# Mixer_to_Low_Pass_Filter.net
KiCad netlist of a schematic drawn in Altium Designer
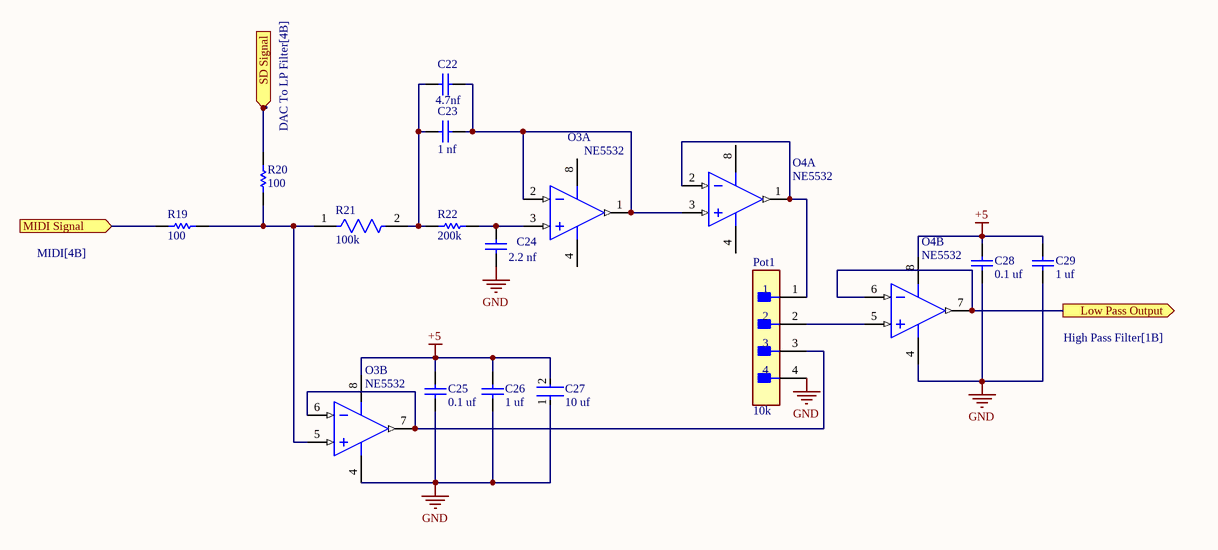
[diagram p0: Mixer to Low Pass Filter.SchDoc]

(export (version "E")
  (design (tool "Eeschema 10.0.6"))
  (components
    (comp (ref "C22")
      (value "4.7nf")
      (footprint "AVX-SA115C104KAR")
      (fields (field (name "TOLERANCE") "±10%") (field (name "MANUFACTURER") "AVX"))
      (libsource (lib "Altium Content Vault") (part "CAP-NP-2"))
    )
    (comp (ref "C23")
      (value "1 nf")
      (footprint "AVX-SA115C104KAR")
      (fields (field (name "TOLERANCE") "±10%") (field (name "MANUFACTURER") "AVX"))
      (libsource (lib "Altium Content Vault") (part "CAP-NP-2"))
    )
    (comp (ref "C24")
      (value "2.2 nf")
      (footprint "AVX-SA115C104KAR")
      (fields (field (name "TOLERANCE") "±10%") (field (name "MANUFACTURER") "AVX"))
      (libsource (lib "Altium Content Vault") (part "CAP-NP-2"))
    )
    (comp (ref "C25")
      (value "0.1 uf")
      (footprint "CAPC2013X135X45ML10T25")
      (description "Chip Capacitor, 0.1 uF, +/- 10%, 50 V, -55 to 125 degC, 0805 (2012 Metric), RoHS, Tape and Reel")
      (fields (field (name "VOLTAGE") "50V") (field (name "TOLERANCE") "10%"))
      (libsource (lib "Altium Content Vault") (part "CAP-NP-2"))
    )
    (comp (ref "C26")
      (value "1 uf")
      (footprint "CAPC2013X145X50LL20T25")
      (fields (field (name "MANUFACTURER") "Kemet") (field (name "PART NUMBER") "C0805C105K4PACTU"))
      (libsource (lib "Altium Content Vault") (part "CAP"))
    )
    (comp (ref "C27")
      (value "10 uf")
      (footprint "FP-C0805C-DG-MFG")
      (description "CAP CER 10UF 10V X5R 0805")
      (fields (field (name "TOLERANCE") "10%") (field (name "MANUFACTURER PART NUMBER") "C0805C106K8PACTU"))
      (libsource (lib "Altium Content Vault") (part "11868f565c42a9108669ba33697ecf6"))
    )
    (comp (ref "C28")
      (value "0.1 uf")
      (footprint "CAPC2013X135X45ML10T25")
      (description "Chip Capacitor, 0.1 uF, +/- 10%, 50 V, -55 to 125 degC, 0805 (2012 Metric), RoHS, Tape and Reel")
      (fields (field (name "VOLTAGE") "50V") (field (name "TOLERANCE") "10%"))
      (libsource (lib "Altium Content Vault") (part "CAP-NP-2"))
    )
    (comp (ref "C29")
      (value "1 uf")
      (footprint "CAPC2013X145X50LL20T25")
      (fields (field (name "MANUFACTURER") "Kemet") (field (name "PART NUMBER") "C0805C105K4PACTU"))
      (libsource (lib "Altium Content Vault") (part "CAP"))
    )
    (comp (ref "O3")
      (value "NE5532")
      (footprint "ONSC-SOIC-8-751-07_V")
      (fields (field (name "MANUFACTURER") "On Semiconductor") (field (name "PARTNUMBER") "NE5532AD8R2G"))
      (libsource (lib "Altium Content Vault") (part "ONSC-NE5532-SOIC-8-751-07"))
    )
    (comp (ref "O4")
      (value "NE5532")
      (footprint "ONSC-SOIC-8-751-07_V")
      (fields (field (name "MANUFACTURER") "On Semiconductor") (field (name "PARTNUMBER") "NE5532AD8R2G"))
      (libsource (lib "Altium Content Vault") (part "ONSC-NE5532-SOIC-8-751-07"))
    )
    (comp (ref "Pot1")
      (value "10k")
      (footprint "FP-B4B-XH-A_LF_SN-MFG")
      (description "CONN HEADER VERT 4POS 2.5MM")
      (libsource (lib "Altium Content Vault") (part "299a8cea1bdcbc3624fe62c390fa72c"))
    )
    (comp (ref "R19")
      (value "100")
      (footprint "RESC2013X60X40ML20T25")
      (fields (field (name "MANUFACTURER") "Panasonic") (field (name "PART NUMBER") "ERA6AEB101V"))
      (libsource (lib "Altium Content Vault") (part "RES"))
    )
    (comp (ref "R20")
      (value "100")
      (footprint "RESC2013X60X40ML20T25")
      (fields (field (name "MANUFACTURER") "Panasonic") (field (name "PART NUMBER") "ERA6AEB101V"))
      (libsource (lib "Altium Content Vault") (part "RES"))
    )
    (comp (ref "R21")
      (value "100k")
      (footprint "FP-RC0805-0_6-IPC_C")
      (description "RES 100K OHM 1% 1/8W 0805")
      (fields (field (name "TOLERANCE") "1%"))
      (libsource (lib "Altium Content Vault") (part "1029c3af85768c4190bb7ad29bc67b5"))
    )
    (comp (ref "R22")
      (value "200k")
      (footprint "RESC2013X60X40LL20T25")
      (fields (field (name "PART NUMBER") "ERA6AEB204V") (field (name "MANUFACTURER") "Panasonic"))
      (libsource (lib "Altium Content Vault") (part "RES"))
    )
  )
  (nets
    (net (code "1") (name "+5") (class "Default")
      (node (ref "C25") (pin "1") (pinfunction "1_1") (pintype "passive"))
      (node (ref "C26") (pin "1") (pinfunction "1_1") (pintype "passive"))
      (node (ref "C27") (pin "2") (pinfunction "2_2") (pintype "passive"))
      (node (ref "C28") (pin "1") (pinfunction "1_1") (pintype "passive"))
      (node (ref "C29") (pin "1") (pinfunction "1_1") (pintype "passive"))
      (node (ref "O3") (pin "8") (pinfunction "V+_8") (pintype "power_in"))
      (node (ref "O4") (pin "8") (pinfunction "V+_8") (pintype "power_in"))
    )
    (net (code "2") (name "/Low Pass Output") (class "Default")
      (node (ref "O4") (pin "6") (pinfunction "INB-_6") (pintype "input"))
      (node (ref "O4") (pin "7") (pinfunction "OUTB_7") (pintype "output"))
    )
    (net (code "3") (name "/MIDI Signal") (class "Default")
      (node (ref "R19") (pin "1") (pinfunction "1_1") (pintype "passive"))
    )
    (net (code "4") (name "/SD Signal") (class "Default")
      (node (ref "R20") (pin "1") (pinfunction "1_1") (pintype "passive"))
    )
    (net (code "5") (name "GND") (class "Default")
      (node (ref "C24") (pin "1") (pinfunction "1_1") (pintype "passive"))
      (node (ref "C25") (pin "2") (pinfunction "2_2") (pintype "passive"))
      (node (ref "C26") (pin "2") (pinfunction "2_2") (pintype "passive"))
      (node (ref "C27") (pin "1") (pinfunction "1_1") (pintype "passive"))
      (node (ref "C28") (pin "2") (pinfunction "2_2") (pintype "passive"))
      (node (ref "C29") (pin "2") (pinfunction "2_2") (pintype "passive"))
      (node (ref "O3") (pin "4") (pinfunction "V-_4") (pintype "power_in"))
      (node (ref "O4") (pin "4") (pinfunction "V-_4") (pintype "power_in"))
      (node (ref "Pot1") (pin "4") (pinfunction "4_4") (pintype "passive"))
    )
    (net (code "6") (name "Net-(C22-Pad1)") (class "Default")
      (node (ref "C22") (pin "1") (pinfunction "1_1") (pintype "passive"))
      (node (ref "C23") (pin "1") (pinfunction "1_1") (pintype "passive"))
      (node (ref "R21") (pin "2") (pinfunction "2_2") (pintype "passive"))
      (node (ref "R22") (pin "1") (pinfunction "1_1") (pintype "passive"))
    )
    (net (code "7") (name "Net-(O3A-INA+)") (class "Default")
      (node (ref "C24") (pin "2") (pinfunction "2_2") (pintype "passive"))
      (node (ref "O3") (pin "3") (pinfunction "INA+_3") (pintype "input"))
      (node (ref "R22") (pin "2") (pinfunction "2_2") (pintype "passive"))
    )
    (net (code "8") (name "Net-(O3A-INA-)") (class "Default")
      (node (ref "C22") (pin "2") (pinfunction "2_2") (pintype "passive"))
      (node (ref "C23") (pin "2") (pinfunction "2_2") (pintype "passive"))
      (node (ref "O3") (pin "1") (pinfunction "OUTA_1") (pintype "output"))
      (node (ref "O3") (pin "2") (pinfunction "INA-_2") (pintype "input"))
      (node (ref "O4") (pin "3") (pinfunction "INA+_3") (pintype "input"))
    )
    (net (code "9") (name "Net-(O3B-INB+)") (class "Default")
      (node (ref "O3") (pin "5") (pinfunction "INB+_5") (pintype "input"))
      (node (ref "R19") (pin "2") (pinfunction "2_2") (pintype "passive"))
      (node (ref "R20") (pin "2") (pinfunction "2_2") (pintype "passive"))
      (node (ref "R21") (pin "1") (pinfunction "1_1") (pintype "passive"))
    )
    (net (code "10") (name "Net-(O3B-INB-)") (class "Default")
      (node (ref "O3") (pin "6") (pinfunction "INB-_6") (pintype "input"))
      (node (ref "O3") (pin "7") (pinfunction "OUTB_7") (pintype "output"))
      (node (ref "Pot1") (pin "3") (pinfunction "3_3") (pintype "passive"))
    )
    (net (code "11") (name "Net-(O4A-INA-)") (class "Default")
      (node (ref "O4") (pin "1") (pinfunction "OUTA_1") (pintype "output"))
      (node (ref "O4") (pin "2") (pinfunction "INA-_2") (pintype "input"))
      (node (ref "Pot1") (pin "1") (pinfunction "1_1") (pintype "passive"))
    )
    (net (code "12") (name "Net-(O4B-INB+)") (class "Default")
      (node (ref "O4") (pin "5") (pinfunction "INB+_5") (pintype "input"))
      (node (ref "Pot1") (pin "2") (pinfunction "2_2") (pintype "passive"))
    )
    (net (code "13") (name "unconnected-(O3A-V+-Pad8)") (class "Default")
      (node (ref "O3") (pin "8") (pinfunction "V+_8") (pintype "power_in"))
    )
    (net (code "14") (name "unconnected-(O3A-V--Pad4)") (class "Default")
      (node (ref "O3") (pin "4") (pinfunction "V-_4") (pintype "power_in"))
    )
    (net (code "15") (name "unconnected-(O4A-V+-Pad8)") (class "Default")
      (node (ref "O4") (pin "8") (pinfunction "V+_8") (pintype "power_in"))
    )
    (net (code "16") (name "unconnected-(O4A-V--Pad4)") (class "Default")
      (node (ref "O4") (pin "4") (pinfunction "V-_4") (pintype "power_in"))
    )
  )
)
